# PLD_AVR_Watchdog.net
KiCad netlist of a schematic drawn in Altium Designer
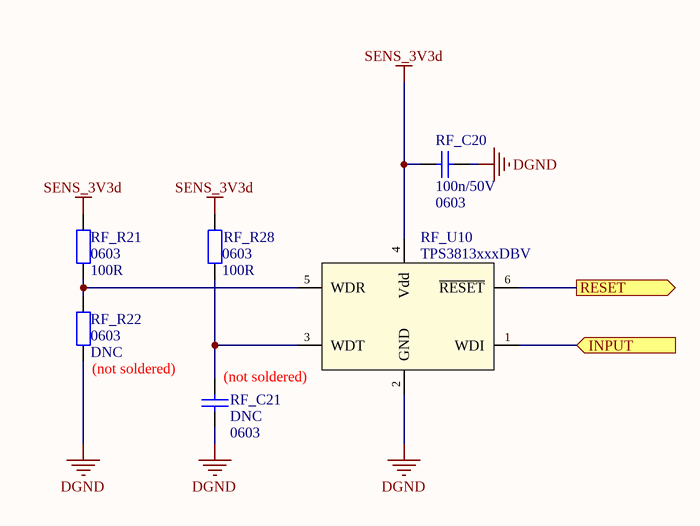
[diagram p0: PLD_AVR_Watchdog.SchDoc]

(export (version "E")
  (design (tool "Eeschema 10.0.6"))
  (components
    (comp (ref "RF_C20")
      (value "100n/50V")
      (footprint "SMD_Capacitor_0603")
      (description "Ceramic Cap Kemet COTS 100n/50V X7R 0603")
      (fields
        (field (name "MANUFACTURER") "Kemet")
        (field (name "MANUFACTURERPARTNUMBER") "C0603T104K5RALTU")
        (field (name "PACKAGE") "0603")
      )
      (libsource (lib "capacitors") (part "Cer_C0603T104K5RALTU"))
    )
    (comp (ref "RF_C21")
      (value "DNC")
      (footprint "SMD_Capacitor_0603")
      (description "Ceramic Cap Kemet COTS 100n/50V X7R 0603")
      (fields
        (field (name "MANUFACTURER") "Kemet")
        (field (name "MANUFACTURERPARTNUMBER") "C0603T104K5RALTU")
        (field (name "PACKAGE") "0603")
      )
      (libsource (lib "capacitors") (part "Cer_C0603T104K5RALTU"))
    )
    (comp (ref "RF_R21")
      (value "0603")
      (footprint "SMD_Resistor_0603")
      (description "Resistor")
      (fields (field (name "ALTIUM_VALUE") "100R") (field (name "PUBLISHER") "Altium Limited"))
      (libsource (lib "Miscellaneous Devices") (part "Res2"))
    )
    (comp (ref "RF_R22")
      (value "0603")
      (footprint "SMD_Resistor_0603")
      (description "Resistor")
      (fields (field (name "ALTIUM_VALUE") "DNC") (field (name "PUBLISHER") "Altium Limited"))
      (libsource (lib "Miscellaneous Devices") (part "Res2"))
    )
    (comp (ref "RF_R28")
      (value "0603")
      (footprint "SMD_Resistor_0603")
      (description "Resistor")
      (fields (field (name "ALTIUM_VALUE") "100R") (field (name "PUBLISHER") "Altium Limited"))
      (libsource (lib "Miscellaneous Devices") (part "Res2"))
    )
    (comp (ref "RF_U10")
      (value "TPS3813xxxDBV")
      (footprint "SOT23-6")
      (description "Processor Supervisory Circuits with Window-Watchdog.")
      (fields (field (name "MANUFACTURER") "Texas Instruments"))
      (libsource (lib "microcircuits_other-functions") (part "TPS3813xxxDBV"))
    )
  )
  (nets
    (net (code "1") (name "/INPUT") (class "Default")
      (node (ref "RF_U10") (pin "1") (pinfunction "WDI_1") (pintype "passive"))
    )
    (net (code "2") (name "/RESET") (class "Default")
      (node (ref "RF_U10") (pin "6") (pinfunction "~{RESET}_6") (pintype "passive"))
    )
    (net (code "3") (name "DGND") (class "Default")
      (node (ref "RF_C20") (pin "2") (pinfunction "2_2") (pintype "passive"))
      (node (ref "RF_C21") (pin "2") (pinfunction "2_2") (pintype "passive"))
      (node (ref "RF_R22") (pin "1") (pinfunction "1_1") (pintype "passive"))
      (node (ref "RF_U10") (pin "2") (pinfunction "GND_2") (pintype "passive"))
    )
    (net (code "4") (name "Net-(RF_U10-WDR)") (class "Default")
      (node (ref "RF_R21") (pin "1") (pinfunction "1_1") (pintype "passive"))
      (node (ref "RF_R22") (pin "2") (pinfunction "2_2") (pintype "passive"))
      (node (ref "RF_U10") (pin "5") (pinfunction "WDR_5") (pintype "passive"))
    )
    (net (code "5") (name "Net-(RF_U10-WDT)") (class "Default")
      (node (ref "RF_C21") (pin "1") (pinfunction "1_1") (pintype "passive"))
      (node (ref "RF_R28") (pin "1") (pinfunction "1_1") (pintype "passive"))
      (node (ref "RF_U10") (pin "3") (pinfunction "WDT_3") (pintype "passive"))
    )
    (net (code "6") (name "SENS_3V3d") (class "Default")
      (node (ref "RF_C20") (pin "1") (pinfunction "1_1") (pintype "passive"))
      (node (ref "RF_R21") (pin "2") (pinfunction "2_2") (pintype "passive"))
      (node (ref "RF_R28") (pin "2") (pinfunction "2_2") (pintype "passive"))
      (node (ref "RF_U10") (pin "4") (pinfunction "Vdd_4") (pintype "passive"))
    )
  )
)
